# Sheet_1.net
KiCad netlist of a schematic drawn in EasyEDA
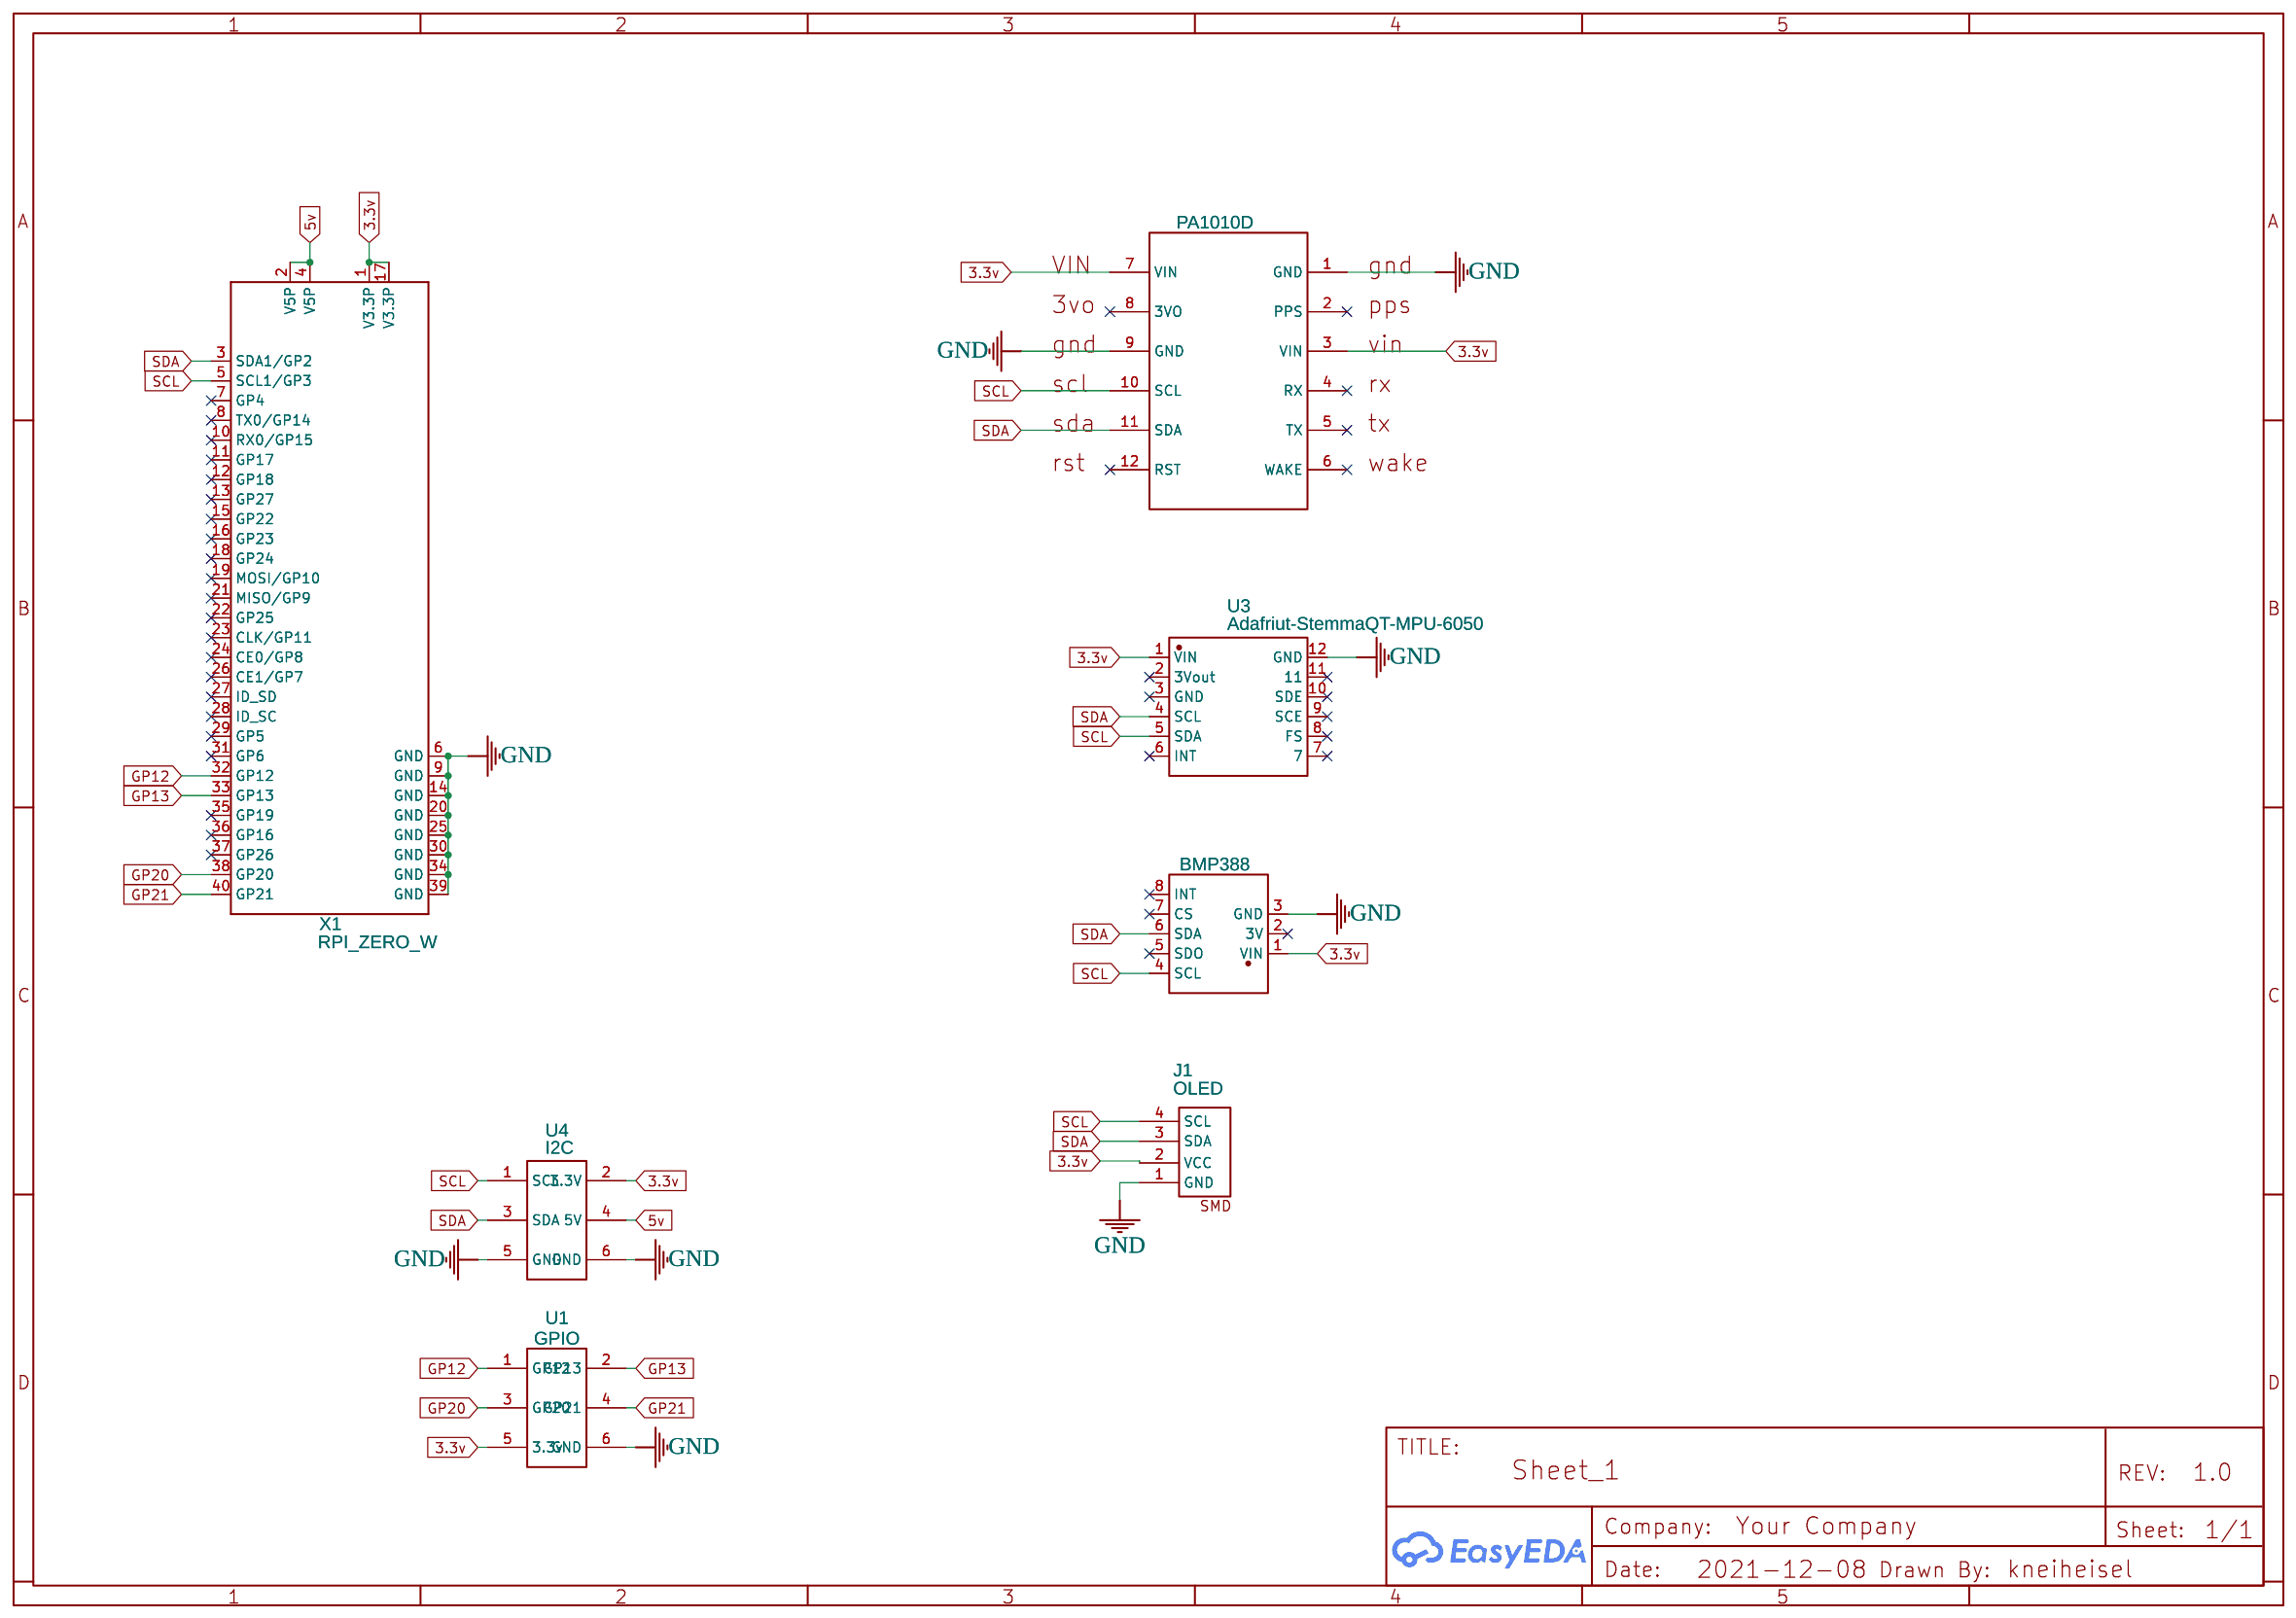
[diagram p0: schematic sheet]

(export (version "E")
  (design (tool "Eeschema 10.0.6"))
  (components
    (comp (ref "J1") (value "OLED") (libsource (lib "") (part "JST SH 4-pin I2C-H")))
    (comp (ref "S1") (value "BMP388") (libsource (lib "") (part "Adafruit BMP388")))
    (comp (ref "U1")
      (value "GPIO")
      (fields (field (name "BOM_Manufacturer Part") "2X3 PINHD"))
      (libsource (lib "") (part "2X3 PINHD_1"))
    )
    (comp (ref "U2") (value "PA1010D") (libsource (lib "") (part "adafruit pa1010d mini gps")))
    (comp (ref "U3")
      (value "Adafriut-StemmaQT-MPU-6050")
      (libsource (lib "") (part "Adafriut-StemmaQT-MPU-6050"))
    )
    (comp (ref "U4")
      (value "I2C")
      (fields (field (name "BOM_Manufacturer Part") "2X3 PINHD"))
      (libsource (lib "") (part "2X3 PINHD"))
    )
    (comp (ref "X1") (value "RPI_ZERO_W") (libsource (lib "") (part "RPI_ZERO_W")))
  )
  (nets
    (net (code "1") (name "3.3v") (class "Default")
      (node (ref "J1") (pin "2") (pinfunction "VCC_2") (pintype "unspecified"))
      (node (ref "S1") (pin "1") (pinfunction "VIN_1") (pintype "unspecified"))
      (node (ref "U1") (pin "5") (pinfunction "3.3v_5") (pintype "unspecified"))
      (node (ref "U2") (pin "3") (pinfunction "VIN_3") (pintype "unspecified"))
      (node (ref "U2") (pin "7") (pinfunction "VIN_7") (pintype "unspecified"))
      (node (ref "U3") (pin "1") (pinfunction "VIN_1") (pintype "unspecified"))
      (node (ref "U4") (pin "2") (pinfunction "3.3V_2") (pintype "unspecified"))
      (node (ref "X1") (pin "1") (pinfunction "V3.3P_1") (pintype "passive"))
      (node (ref "X1") (pin "17") (pinfunction "V3.3P_17") (pintype "unspecified"))
    )
    (net (code "2") (name "5v") (class "Default")
      (node (ref "U4") (pin "4") (pinfunction "5V_4") (pintype "unspecified"))
      (node (ref "X1") (pin "2") (pinfunction "V5P_2") (pintype "passive"))
      (node (ref "X1") (pin "4") (pinfunction "V5P_4") (pintype "unspecified"))
    )
    (net (code "3") (name "GND") (class "Default")
      (node (ref "J1") (pin "1") (pinfunction "GND_1") (pintype "unspecified"))
      (node (ref "S1") (pin "3") (pinfunction "GND_3") (pintype "unspecified"))
      (node (ref "U1") (pin "6") (pinfunction "GND_6") (pintype "unspecified"))
      (node (ref "U2") (pin "1") (pinfunction "GND_1") (pintype "unspecified"))
      (node (ref "U2") (pin "9") (pinfunction "GND_9") (pintype "unspecified"))
      (node (ref "U3") (pin "12") (pinfunction "GND_12") (pintype "unspecified"))
      (node (ref "U4") (pin "5") (pinfunction "GND_5") (pintype "unspecified"))
      (node (ref "U4") (pin "6") (pinfunction "GND_6") (pintype "unspecified"))
      (node (ref "X1") (pin "14") (pinfunction "GND_14") (pintype "unspecified"))
      (node (ref "X1") (pin "20") (pinfunction "GND_20") (pintype "unspecified"))
      (node (ref "X1") (pin "25") (pinfunction "GND_25") (pintype "unspecified"))
      (node (ref "X1") (pin "30") (pinfunction "GND_30") (pintype "unspecified"))
      (node (ref "X1") (pin "34") (pinfunction "GND_34") (pintype "unspecified"))
      (node (ref "X1") (pin "39") (pinfunction "GND_39") (pintype "unspecified"))
      (node (ref "X1") (pin "6") (pinfunction "GND_6") (pintype "passive"))
      (node (ref "X1") (pin "9") (pinfunction "GND_9") (pintype "unspecified"))
    )
    (net (code "4") (name "GP12") (class "Default")
      (node (ref "U1") (pin "1") (pinfunction "GP12_1") (pintype "unspecified"))
      (node (ref "X1") (pin "32") (pinfunction "GP12_32") (pintype "unspecified"))
    )
    (net (code "5") (name "GP13") (class "Default")
      (node (ref "U1") (pin "2") (pinfunction "GP13_2") (pintype "unspecified"))
      (node (ref "X1") (pin "33") (pinfunction "GP13_33") (pintype "unspecified"))
    )
    (net (code "6") (name "GP20") (class "Default")
      (node (ref "U1") (pin "3") (pinfunction "GP20_3") (pintype "unspecified"))
      (node (ref "X1") (pin "38") (pinfunction "GP20_38") (pintype "unspecified"))
    )
    (net (code "7") (name "GP21") (class "Default")
      (node (ref "U1") (pin "4") (pinfunction "GP21_4") (pintype "unspecified"))
      (node (ref "X1") (pin "40") (pinfunction "GP21_40") (pintype "unspecified"))
    )
    (net (code "8") (name "SCL") (class "Default")
      (node (ref "J1") (pin "4") (pinfunction "SCL_4") (pintype "unspecified"))
      (node (ref "S1") (pin "4") (pinfunction "SCL_4") (pintype "unspecified"))
      (node (ref "U2") (pin "10") (pinfunction "SCL_10") (pintype "unspecified"))
      (node (ref "U3") (pin "5") (pinfunction "SDA_5") (pintype "unspecified"))
      (node (ref "U4") (pin "1") (pinfunction "SCL_1") (pintype "unspecified"))
      (node (ref "X1") (pin "5") (pinfunction "SCL1/GP3_5") (pintype "unspecified"))
    )
    (net (code "9") (name "SDA") (class "Default")
      (node (ref "J1") (pin "3") (pinfunction "SDA_3") (pintype "unspecified"))
      (node (ref "S1") (pin "6") (pinfunction "SDA_6") (pintype "unspecified"))
      (node (ref "U2") (pin "11") (pinfunction "SDA_11") (pintype "unspecified"))
      (node (ref "U3") (pin "4") (pinfunction "SCL_4") (pintype "unspecified"))
      (node (ref "U4") (pin "3") (pinfunction "SDA_3") (pintype "unspecified"))
      (node (ref "X1") (pin "3") (pinfunction "SDA1/GP2_3") (pintype "unspecified"))
    )
    (net (code "10") (name "unconnected-(S1-3V-Pad2)") (class "Default")
      (node (ref "S1") (pin "2") (pinfunction "3V_2") (pintype "unspecified+no_connect"))
    )
    (net (code "11") (name "unconnected-(S1-CS-Pad7)") (class "Default")
      (node (ref "S1") (pin "7") (pinfunction "CS_7") (pintype "unspecified+no_connect"))
    )
    (net (code "12") (name "unconnected-(S1-INT-Pad8)") (class "Default")
      (node (ref "S1") (pin "8") (pinfunction "INT_8") (pintype "unspecified+no_connect"))
    )
    (net (code "13") (name "unconnected-(S1-SDO-Pad5)") (class "Default")
      (node (ref "S1") (pin "5") (pinfunction "SDO_5") (pintype "unspecified+no_connect"))
    )
    (net (code "14") (name "unconnected-(U2-3VO-Pad8)") (class "Default")
      (node (ref "U2") (pin "8") (pinfunction "3VO_8") (pintype "unspecified+no_connect"))
    )
    (net (code "15") (name "unconnected-(U2-PPS-Pad2)") (class "Default")
      (node (ref "U2") (pin "2") (pinfunction "PPS_2") (pintype "unspecified+no_connect"))
    )
    (net (code "16") (name "unconnected-(U2-RST-Pad12)") (class "Default")
      (node (ref "U2") (pin "12") (pinfunction "RST_12") (pintype "unspecified+no_connect"))
    )
    (net (code "17") (name "unconnected-(U2-RX-Pad4)") (class "Default")
      (node (ref "U2") (pin "4") (pinfunction "RX_4") (pintype "unspecified+no_connect"))
    )
    (net (code "18") (name "unconnected-(U2-TX-Pad5)") (class "Default")
      (node (ref "U2") (pin "5") (pinfunction "TX_5") (pintype "unspecified+no_connect"))
    )
    (net (code "19") (name "unconnected-(U2-WAKE-Pad6)") (class "Default")
      (node (ref "U2") (pin "6") (pinfunction "WAKE_6") (pintype "unspecified+no_connect"))
    )
    (net (code "20") (name "unconnected-(U3-3Vout-Pad2)") (class "Default")
      (node (ref "U3") (pin "2") (pinfunction "3Vout_2") (pintype "unspecified+no_connect"))
    )
    (net (code "21") (name "unconnected-(U3-FS-Pad8)") (class "Default")
      (node (ref "U3") (pin "8") (pinfunction "FS_8") (pintype "unspecified+no_connect"))
    )
    (net (code "22") (name "unconnected-(U3-GND-Pad3)") (class "Default")
      (node (ref "U3") (pin "3") (pinfunction "GND_3") (pintype "unspecified+no_connect"))
    )
    (net (code "23") (name "unconnected-(U3-INT-Pad6)") (class "Default")
      (node (ref "U3") (pin "6") (pinfunction "INT_6") (pintype "unspecified+no_connect"))
    )
    (net (code "24") (name "unconnected-(U3-Pad7)") (class "Default")
      (node (ref "U3") (pin "7") (pinfunction "7_7") (pintype "unspecified+no_connect"))
    )
    (net (code "25") (name "unconnected-(U3-Pad11)") (class "Default")
      (node (ref "U3") (pin "11") (pinfunction "11_11") (pintype "unspecified+no_connect"))
    )
    (net (code "26") (name "unconnected-(U3-SCE-Pad9)") (class "Default")
      (node (ref "U3") (pin "9") (pinfunction "SCE_9") (pintype "unspecified+no_connect"))
    )
    (net (code "27") (name "unconnected-(U3-SDE-Pad10)") (class "Default")
      (node (ref "U3") (pin "10") (pinfunction "SDE_10") (pintype "unspecified+no_connect"))
    )
    (net (code "28") (name "unconnected-(X1-CE0{slash}GP8-Pad24)") (class "Default")
      (node (ref "X1") (pin "24") (pinfunction "CE0/GP8_24") (pintype "unspecified+no_connect"))
    )
    (net (code "29") (name "unconnected-(X1-CE1{slash}GP7-Pad26)") (class "Default")
      (node (ref "X1") (pin "26") (pinfunction "CE1/GP7_26") (pintype "unspecified+no_connect"))
    )
    (net (code "30") (name "unconnected-(X1-CLK{slash}GP11-Pad23)") (class "Default")
      (node (ref "X1") (pin "23") (pinfunction "CLK/GP11_23") (pintype "unspecified+no_connect"))
    )
    (net (code "31") (name "unconnected-(X1-GP4-Pad7)") (class "Default")
      (node (ref "X1") (pin "7") (pinfunction "GP4_7") (pintype "unspecified+no_connect"))
    )
    (net (code "32") (name "unconnected-(X1-GP5-Pad29)") (class "Default")
      (node (ref "X1") (pin "29") (pinfunction "GP5_29") (pintype "unspecified+no_connect"))
    )
    (net (code "33") (name "unconnected-(X1-GP6-Pad31)") (class "Default")
      (node (ref "X1") (pin "31") (pinfunction "GP6_31") (pintype "unspecified+no_connect"))
    )
    (net (code "34") (name "unconnected-(X1-GP16-Pad36)") (class "Default")
      (node (ref "X1") (pin "36") (pinfunction "GP16_36") (pintype "unspecified+no_connect"))
    )
    (net (code "35") (name "unconnected-(X1-GP17-Pad11)") (class "Default")
      (node (ref "X1") (pin "11") (pinfunction "GP17_11") (pintype "unspecified+no_connect"))
    )
    (net (code "36") (name "unconnected-(X1-GP18-Pad12)") (class "Default")
      (node (ref "X1") (pin "12") (pinfunction "GP18_12") (pintype "unspecified+no_connect"))
    )
    (net (code "37") (name "unconnected-(X1-GP19-Pad35)") (class "Default")
      (node (ref "X1") (pin "35") (pinfunction "GP19_35") (pintype "unspecified+no_connect"))
    )
    (net (code "38") (name "unconnected-(X1-GP22-Pad15)") (class "Default")
      (node (ref "X1") (pin "15") (pinfunction "GP22_15") (pintype "unspecified+no_connect"))
    )
    (net (code "39") (name "unconnected-(X1-GP23-Pad16)") (class "Default")
      (node (ref "X1") (pin "16") (pinfunction "GP23_16") (pintype "unspecified+no_connect"))
    )
    (net (code "40") (name "unconnected-(X1-GP24-Pad18)") (class "Default")
      (node (ref "X1") (pin "18") (pinfunction "GP24_18") (pintype "unspecified+no_connect"))
    )
    (net (code "41") (name "unconnected-(X1-GP25-Pad22)") (class "Default")
      (node (ref "X1") (pin "22") (pinfunction "GP25_22") (pintype "unspecified+no_connect"))
    )
    (net (code "42") (name "unconnected-(X1-GP26-Pad37)") (class "Default")
      (node (ref "X1") (pin "37") (pinfunction "GP26_37") (pintype "unspecified+no_connect"))
    )
    (net (code "43") (name "unconnected-(X1-GP27-Pad13)") (class "Default")
      (node (ref "X1") (pin "13") (pinfunction "GP27_13") (pintype "unspecified+no_connect"))
    )
    (net (code "44") (name "unconnected-(X1-ID_SC-Pad28)") (class "Default")
      (node (ref "X1") (pin "28") (pinfunction "ID_SC_28") (pintype "unspecified+no_connect"))
    )
    (net (code "45") (name "unconnected-(X1-ID_SD-Pad27)") (class "Default")
      (node (ref "X1") (pin "27") (pinfunction "ID_SD_27") (pintype "unspecified+no_connect"))
    )
    (net (code "46") (name "unconnected-(X1-MISO{slash}GP9-Pad21)") (class "Default")
      (node (ref "X1") (pin "21") (pinfunction "MISO/GP9_21") (pintype "unspecified+no_connect"))
    )
    (net (code "47") (name "unconnected-(X1-MOSI{slash}GP10-Pad19)") (class "Default")
      (node (ref "X1") (pin "19") (pinfunction "MOSI/GP10_19") (pintype "unspecified+no_connect"))
    )
    (net (code "48") (name "unconnected-(X1-RX0{slash}GP15-Pad10)") (class "Default")
      (node (ref "X1") (pin "10") (pinfunction "RX0/GP15_10") (pintype "unspecified+no_connect"))
    )
    (net (code "49") (name "unconnected-(X1-TX0{slash}GP14-Pad8)") (class "Default")
      (node (ref "X1") (pin "8") (pinfunction "TX0/GP14_8") (pintype "unspecified+no_connect"))
    )
  )
)
